# sunjar-v1_0.net
KiCad netlist of a schematic drawn in EAGLE
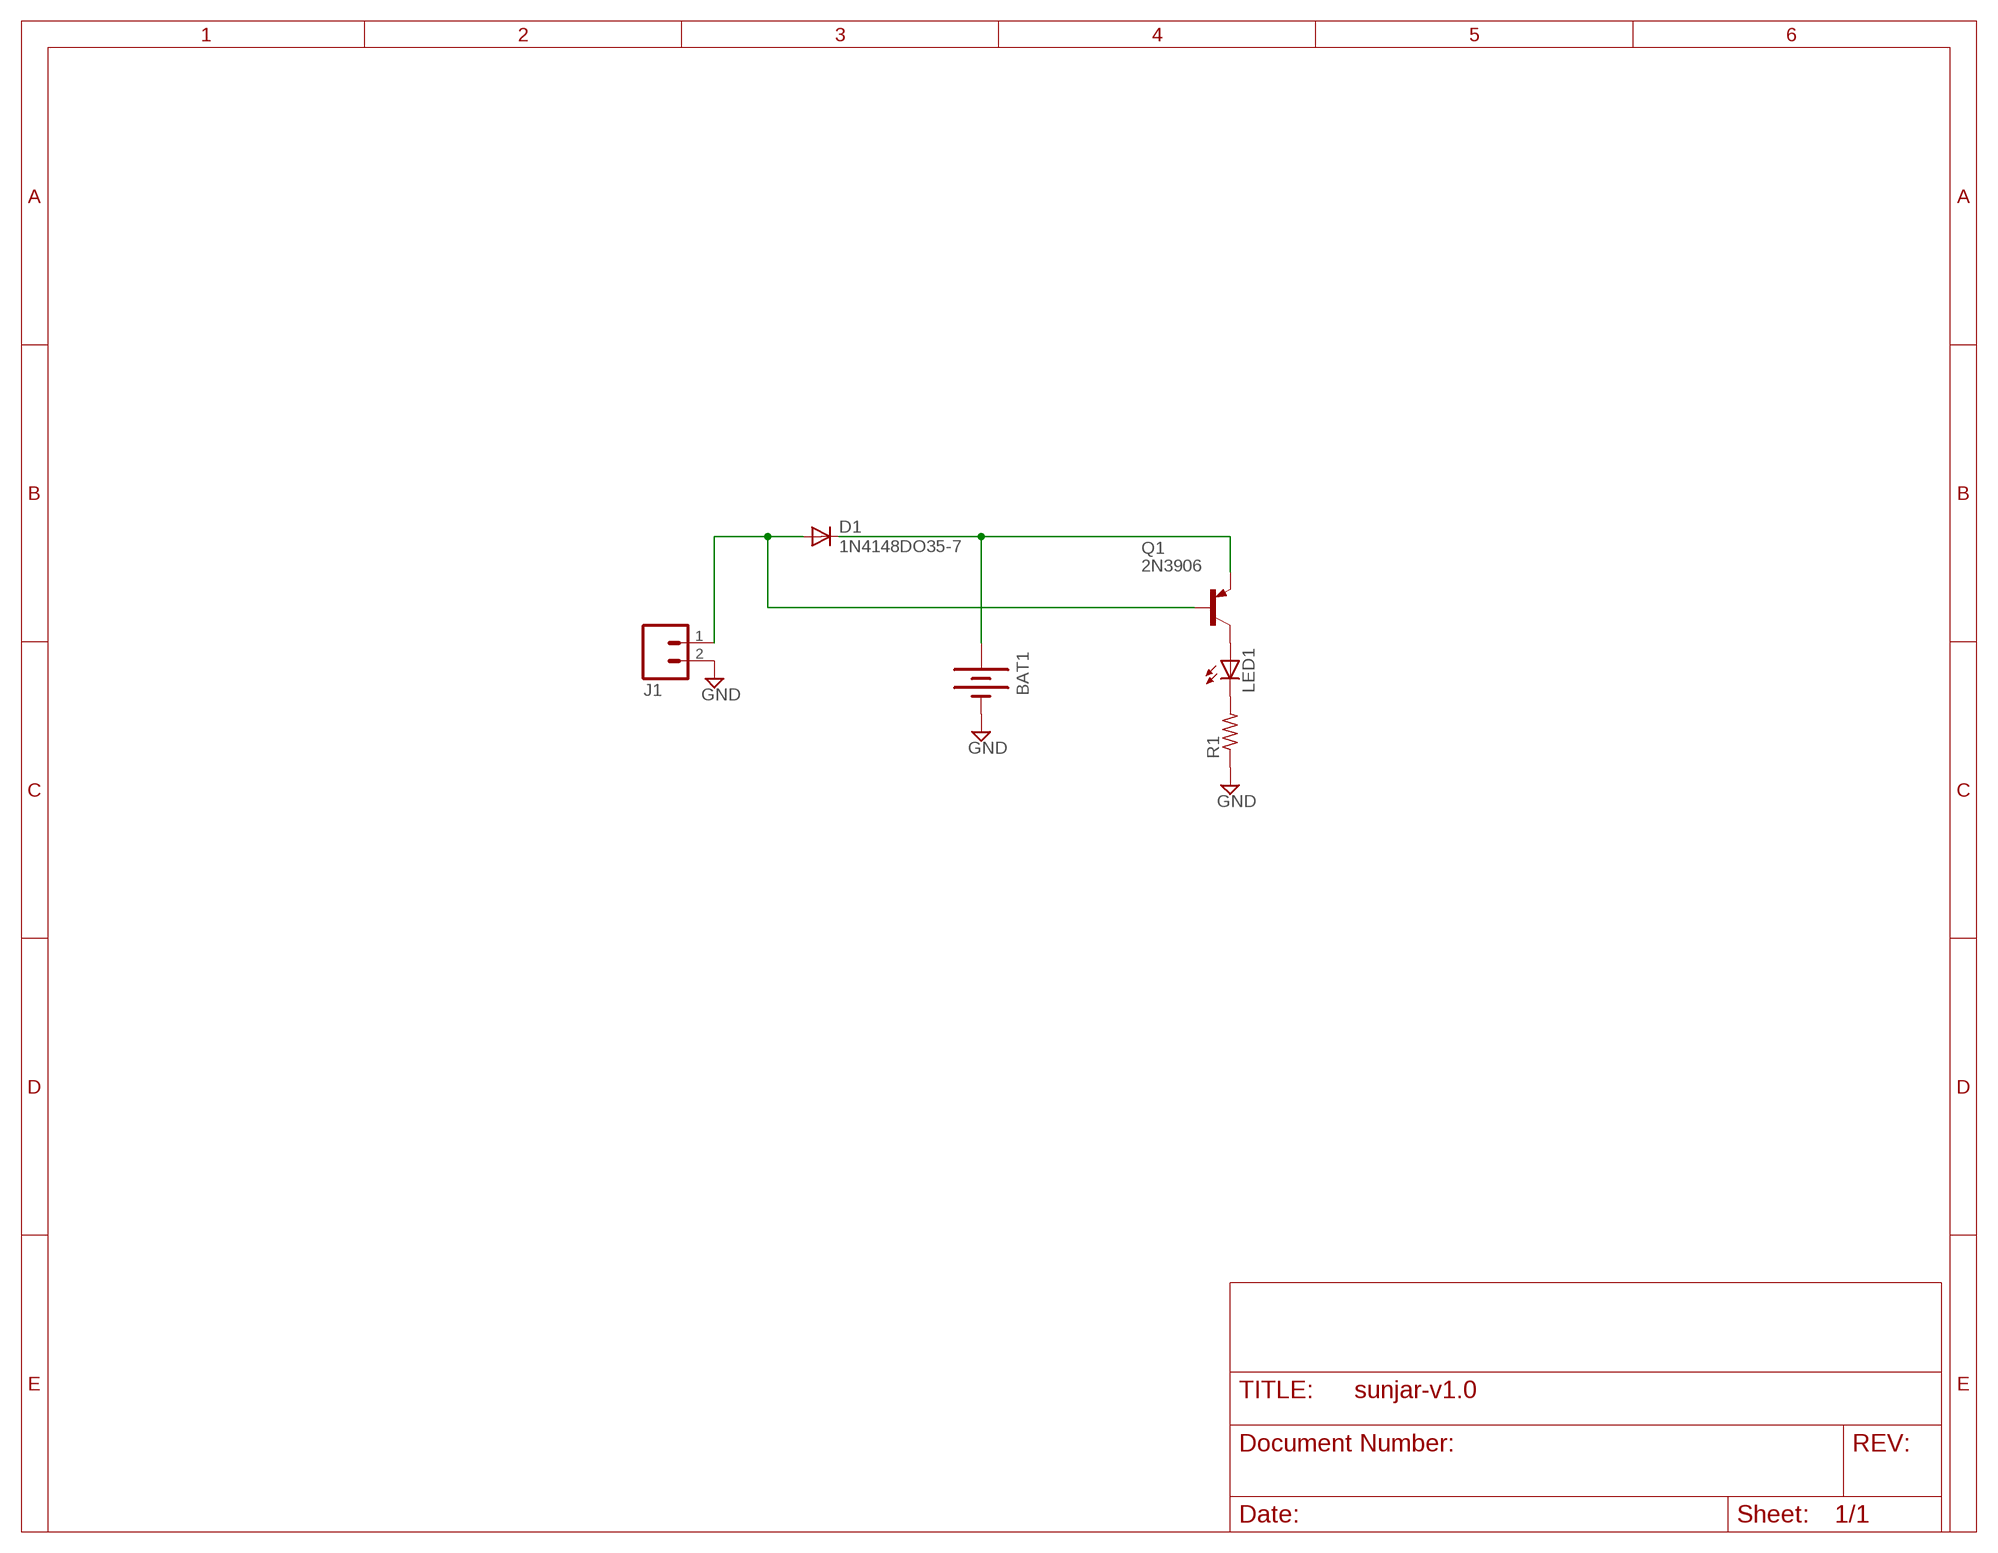
[diagram p0: schematic, sheet 1]

(export (version "E")
  (design (tool "Eeschema 10.0.6"))
  (components
    (comp (ref "BAT1")
      (value "BATTERY245PTH")
      (footprint "eagle-import:BATTCON_245MM_PTH")
      (libsource (lib "eagle-import") (part "BATTERY245PTH"))
    )
    (comp (ref "D1")
      (value "1N4148DO35-7")
      (footprint "eagle-import:DO35-7")
      (libsource (lib "eagle-import") (part "1N4148DO35-7"))
    )
    (comp (ref "J1")
      (value "M02PTH")
      (footprint "eagle-import:1X02")
      (libsource (lib "eagle-import") (part "M02PTH"))
    )
    (comp (ref "LED1")
      (value "LED5MM")
      (footprint "eagle-import:LED5MM")
      (libsource (lib "eagle-import") (part "LED5MM"))
    )
    (comp (ref "Q1")
      (value "2N3906")
      (footprint "eagle-import:TO92")
      (libsource (lib "eagle-import") (part "2N3906"))
    )
    (comp (ref "R1")
      (value "R-US_0207/10")
      (footprint "eagle-import:0207_10")
      (libsource (lib "eagle-import") (part "R-US_0207/10"))
    )
  )
  (nets
    (net (code "1") (name "GND") (class "Default")
      (node (ref "BAT1") (pin "2") (pinfunction "-_2") (pintype "power_in"))
      (node (ref "J1") (pin "2") (pinfunction "2_2") (pintype "passive"))
      (node (ref "R1") (pin "1") (pinfunction "1_1") (pintype "passive"))
    )
    (net (code "2") (name "Net-(BAT1-+)") (class "Default")
      (node (ref "BAT1") (pin "3") (pinfunction "+_3") (pintype "power_in"))
      (node (ref "D1") (pin "C") (pinfunction "C_C") (pintype "passive"))
      (node (ref "Q1") (pin "3") (pinfunction "E_3") (pintype "passive"))
    )
    (net (code "3") (name "Net-(LED1-C)") (class "Default")
      (node (ref "LED1") (pin "K") (pinfunction "C_K") (pintype "passive"))
      (node (ref "R1") (pin "2") (pinfunction "2_2") (pintype "passive"))
    )
    (net (code "4") (name "Net-(Q1-B)") (class "Default")
      (node (ref "D1") (pin "A") (pinfunction "A_A") (pintype "passive"))
      (node (ref "J1") (pin "1") (pinfunction "1_1") (pintype "passive"))
      (node (ref "Q1") (pin "2") (pinfunction "B_2") (pintype "passive"))
    )
    (net (code "5") (name "Net-(Q1-C)") (class "Default")
      (node (ref "LED1") (pin "A") (pinfunction "A_A") (pintype "passive"))
      (node (ref "Q1") (pin "1") (pinfunction "C_1") (pintype "passive"))
    )
  )
)
